# NixieBoard.net
KiCad netlist of a schematic drawn in EAGLE
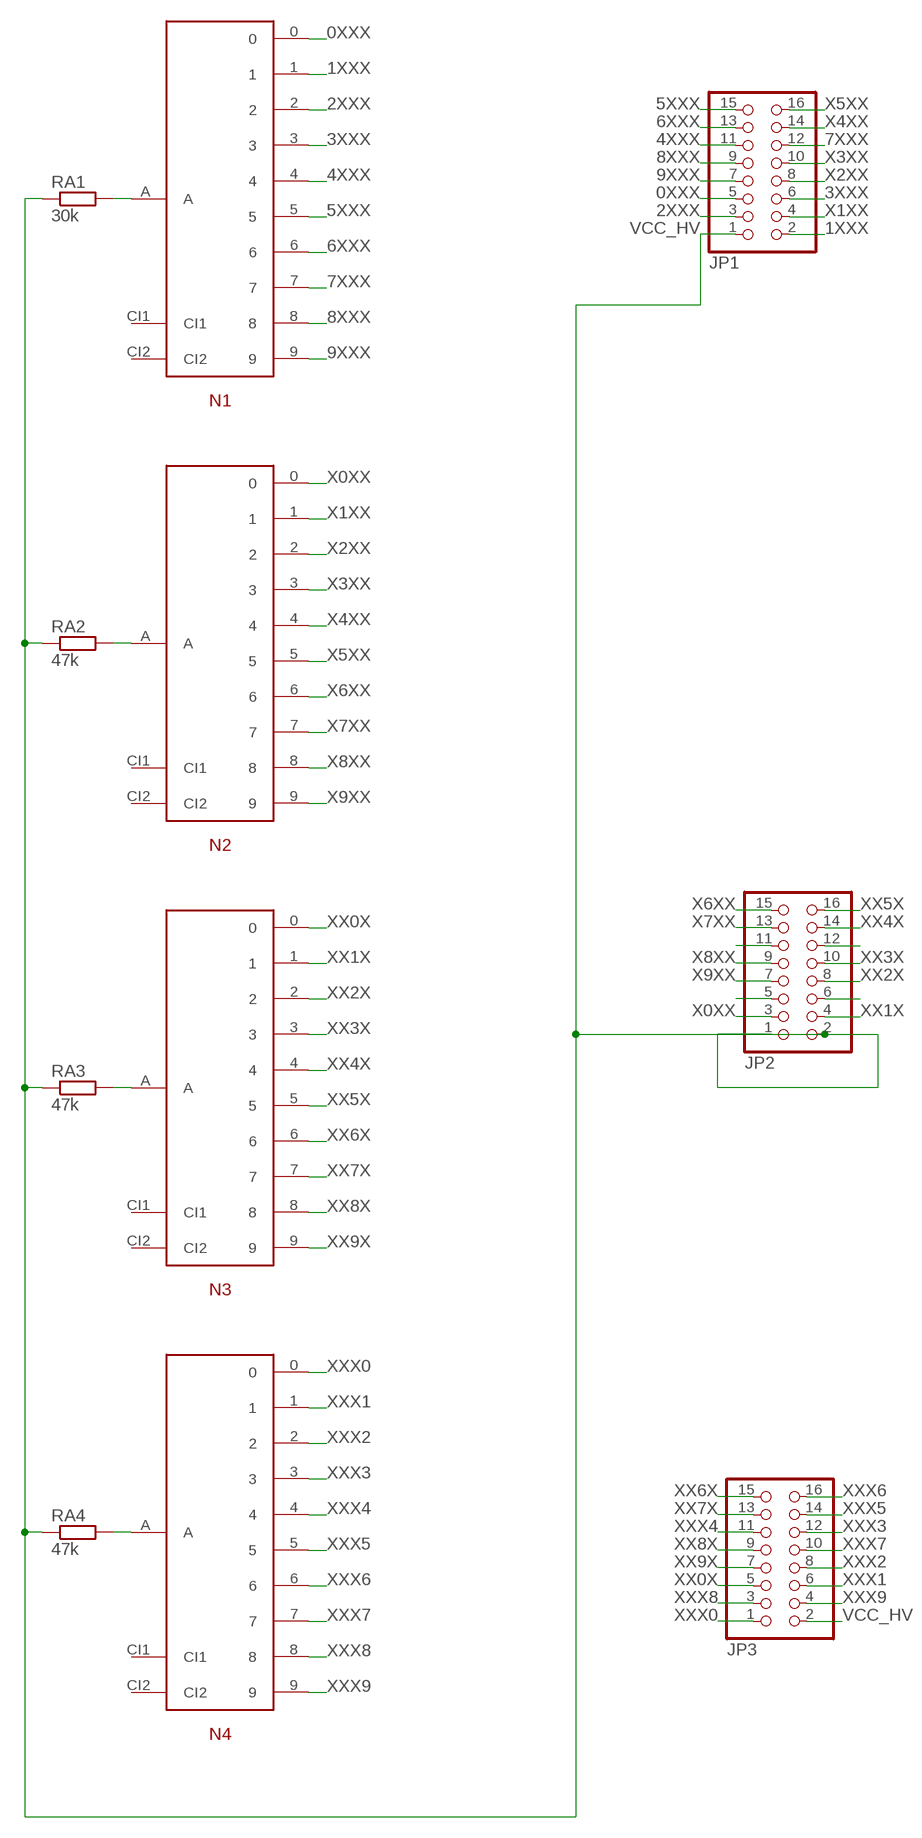
[diagram p0: schematic, sheet 1]

(export (version "E")
  (design (tool "Eeschema 10.0.6"))
  (components
    (comp (ref "JP1")
      (value "PINHD-2X8")
      (footprint "eagle-import:2X08")
      (libsource (lib "eagle-import") (part "PINHD-2X8"))
    )
    (comp (ref "JP2")
      (value "PINHD-2X8")
      (footprint "eagle-import:2X08")
      (libsource (lib "eagle-import") (part "PINHD-2X8"))
    )
    (comp (ref "JP3")
      (value "PINHD-2X8")
      (footprint "eagle-import:2X08")
      (libsource (lib "eagle-import") (part "PINHD-2X8"))
    )
    (comp (ref "N1")
      (value "F9057TUBE")
      (footprint "eagle-import:F9057PIN")
      (libsource (lib "eagle-import") (part "F9057TUBE"))
    )
    (comp (ref "N2")
      (value "F9057TUBE")
      (footprint "eagle-import:F9057PIN")
      (libsource (lib "eagle-import") (part "F9057TUBE"))
    )
    (comp (ref "N3")
      (value "F9057TUBE")
      (footprint "eagle-import:F9057PIN")
      (libsource (lib "eagle-import") (part "F9057TUBE"))
    )
    (comp (ref "N4")
      (value "F9057TUBE")
      (footprint "eagle-import:F9057PIN")
      (libsource (lib "eagle-import") (part "F9057TUBE"))
    )
    (comp (ref "RA1")
      (value "30k")
      (footprint "eagle-import:R2010")
      (libsource (lib "eagle-import") (part "R-EU_R2010"))
    )
    (comp (ref "RA2")
      (value "47k")
      (footprint "eagle-import:R2010")
      (libsource (lib "eagle-import") (part "R-EU_R2010"))
    )
    (comp (ref "RA3")
      (value "47k")
      (footprint "eagle-import:R2010")
      (libsource (lib "eagle-import") (part "R-EU_R2010"))
    )
    (comp (ref "RA4")
      (value "47k")
      (footprint "eagle-import:R2010")
      (libsource (lib "eagle-import") (part "R-EU_R2010"))
    )
  )
  (nets
    (net (code "1") (name "/0XXX") (class "Default")
      (node (ref "JP1") (pin "5") (pinfunction "5_5") (pintype "passive"))
      (node (ref "N1") (pin "0") (pinfunction "0_0") (pintype "bidirectional"))
    )
    (net (code "2") (name "/1XXX") (class "Default")
      (node (ref "JP1") (pin "2") (pinfunction "2_2") (pintype "passive"))
      (node (ref "N1") (pin "1") (pinfunction "1_1") (pintype "bidirectional"))
    )
    (net (code "3") (name "/2XXX") (class "Default")
      (node (ref "JP1") (pin "3") (pinfunction "3_3") (pintype "passive"))
      (node (ref "N1") (pin "2") (pinfunction "2_2") (pintype "bidirectional"))
    )
    (net (code "4") (name "/3XXX") (class "Default")
      (node (ref "JP1") (pin "6") (pinfunction "6_6") (pintype "passive"))
      (node (ref "N1") (pin "3") (pinfunction "3_3") (pintype "bidirectional"))
    )
    (net (code "5") (name "/4XXX") (class "Default")
      (node (ref "JP1") (pin "11") (pinfunction "11_11") (pintype "passive"))
      (node (ref "N1") (pin "4") (pinfunction "4_4") (pintype "bidirectional"))
    )
    (net (code "6") (name "/5XXX") (class "Default")
      (node (ref "JP1") (pin "15") (pinfunction "15_15") (pintype "passive"))
      (node (ref "N1") (pin "5") (pinfunction "5_5") (pintype "bidirectional"))
    )
    (net (code "7") (name "/6XXX") (class "Default")
      (node (ref "JP1") (pin "13") (pinfunction "13_13") (pintype "passive"))
      (node (ref "N1") (pin "6") (pinfunction "6_6") (pintype "bidirectional"))
    )
    (net (code "8") (name "/7XXX") (class "Default")
      (node (ref "JP1") (pin "12") (pinfunction "12_12") (pintype "passive"))
      (node (ref "N1") (pin "7") (pinfunction "7_7") (pintype "bidirectional"))
    )
    (net (code "9") (name "/8XXX") (class "Default")
      (node (ref "JP1") (pin "9") (pinfunction "9_9") (pintype "passive"))
      (node (ref "N1") (pin "8") (pinfunction "8_8") (pintype "bidirectional"))
    )
    (net (code "10") (name "/9XXX") (class "Default")
      (node (ref "JP1") (pin "7") (pinfunction "7_7") (pintype "passive"))
      (node (ref "N1") (pin "9") (pinfunction "9_9") (pintype "bidirectional"))
    )
    (net (code "11") (name "/VCC_HV") (class "Default")
      (node (ref "JP1") (pin "1") (pinfunction "1_1") (pintype "passive"))
      (node (ref "JP2") (pin "1") (pinfunction "1_1") (pintype "passive"))
      (node (ref "JP2") (pin "2") (pinfunction "2_2") (pintype "passive"))
      (node (ref "JP3") (pin "2") (pinfunction "2_2") (pintype "passive"))
      (node (ref "RA1") (pin "1") (pinfunction "1_1") (pintype "passive"))
      (node (ref "RA2") (pin "1") (pinfunction "1_1") (pintype "passive"))
      (node (ref "RA3") (pin "1") (pinfunction "1_1") (pintype "passive"))
      (node (ref "RA4") (pin "1") (pinfunction "1_1") (pintype "passive"))
    )
    (net (code "12") (name "/X0XX") (class "Default")
      (node (ref "JP2") (pin "3") (pinfunction "3_3") (pintype "passive"))
      (node (ref "N2") (pin "0") (pinfunction "0_0") (pintype "bidirectional"))
    )
    (net (code "13") (name "/X1XX") (class "Default")
      (node (ref "JP1") (pin "4") (pinfunction "4_4") (pintype "passive"))
      (node (ref "N2") (pin "1") (pinfunction "1_1") (pintype "bidirectional"))
    )
    (net (code "14") (name "/X2XX") (class "Default")
      (node (ref "JP1") (pin "8") (pinfunction "8_8") (pintype "passive"))
      (node (ref "N2") (pin "2") (pinfunction "2_2") (pintype "bidirectional"))
    )
    (net (code "15") (name "/X3XX") (class "Default")
      (node (ref "JP1") (pin "10") (pinfunction "10_10") (pintype "passive"))
      (node (ref "N2") (pin "3") (pinfunction "3_3") (pintype "bidirectional"))
    )
    (net (code "16") (name "/X4XX") (class "Default")
      (node (ref "JP1") (pin "14") (pinfunction "14_14") (pintype "passive"))
      (node (ref "N2") (pin "4") (pinfunction "4_4") (pintype "bidirectional"))
    )
    (net (code "17") (name "/X5XX") (class "Default")
      (node (ref "JP1") (pin "16") (pinfunction "16_16") (pintype "passive"))
      (node (ref "N2") (pin "5") (pinfunction "5_5") (pintype "bidirectional"))
    )
    (net (code "18") (name "/X6XX") (class "Default")
      (node (ref "JP2") (pin "15") (pinfunction "15_15") (pintype "passive"))
      (node (ref "N2") (pin "6") (pinfunction "6_6") (pintype "bidirectional"))
    )
    (net (code "19") (name "/X7XX") (class "Default")
      (node (ref "JP2") (pin "13") (pinfunction "13_13") (pintype "passive"))
      (node (ref "N2") (pin "7") (pinfunction "7_7") (pintype "bidirectional"))
    )
    (net (code "20") (name "/X8XX") (class "Default")
      (node (ref "JP2") (pin "9") (pinfunction "9_9") (pintype "passive"))
      (node (ref "N2") (pin "8") (pinfunction "8_8") (pintype "bidirectional"))
    )
    (net (code "21") (name "/X9XX") (class "Default")
      (node (ref "JP2") (pin "7") (pinfunction "7_7") (pintype "passive"))
      (node (ref "N2") (pin "9") (pinfunction "9_9") (pintype "bidirectional"))
    )
    (net (code "22") (name "/XX0X") (class "Default")
      (node (ref "JP3") (pin "5") (pinfunction "5_5") (pintype "passive"))
      (node (ref "N3") (pin "0") (pinfunction "0_0") (pintype "bidirectional"))
    )
    (net (code "23") (name "/XX1X") (class "Default")
      (node (ref "JP2") (pin "4") (pinfunction "4_4") (pintype "passive"))
      (node (ref "N3") (pin "1") (pinfunction "1_1") (pintype "bidirectional"))
    )
    (net (code "24") (name "/XX2X") (class "Default")
      (node (ref "JP2") (pin "8") (pinfunction "8_8") (pintype "passive"))
      (node (ref "N3") (pin "2") (pinfunction "2_2") (pintype "bidirectional"))
    )
    (net (code "25") (name "/XX3X") (class "Default")
      (node (ref "JP2") (pin "10") (pinfunction "10_10") (pintype "passive"))
      (node (ref "N3") (pin "3") (pinfunction "3_3") (pintype "bidirectional"))
    )
    (net (code "26") (name "/XX4X") (class "Default")
      (node (ref "JP2") (pin "14") (pinfunction "14_14") (pintype "passive"))
      (node (ref "N3") (pin "4") (pinfunction "4_4") (pintype "bidirectional"))
    )
    (net (code "27") (name "/XX5X") (class "Default")
      (node (ref "JP2") (pin "16") (pinfunction "16_16") (pintype "passive"))
      (node (ref "N3") (pin "5") (pinfunction "5_5") (pintype "bidirectional"))
    )
    (net (code "28") (name "/XX6X") (class "Default")
      (node (ref "JP3") (pin "15") (pinfunction "15_15") (pintype "passive"))
      (node (ref "N3") (pin "6") (pinfunction "6_6") (pintype "bidirectional"))
    )
    (net (code "29") (name "/XX7X") (class "Default")
      (node (ref "JP3") (pin "13") (pinfunction "13_13") (pintype "passive"))
      (node (ref "N3") (pin "7") (pinfunction "7_7") (pintype "bidirectional"))
    )
    (net (code "30") (name "/XX8X") (class "Default")
      (node (ref "JP3") (pin "9") (pinfunction "9_9") (pintype "passive"))
      (node (ref "N3") (pin "8") (pinfunction "8_8") (pintype "bidirectional"))
    )
    (net (code "31") (name "/XX9X") (class "Default")
      (node (ref "JP3") (pin "7") (pinfunction "7_7") (pintype "passive"))
      (node (ref "N3") (pin "9") (pinfunction "9_9") (pintype "bidirectional"))
    )
    (net (code "32") (name "/XXX0") (class "Default")
      (node (ref "JP3") (pin "1") (pinfunction "1_1") (pintype "passive"))
      (node (ref "N4") (pin "0") (pinfunction "0_0") (pintype "bidirectional"))
    )
    (net (code "33") (name "/XXX1") (class "Default")
      (node (ref "JP3") (pin "6") (pinfunction "6_6") (pintype "passive"))
      (node (ref "N4") (pin "1") (pinfunction "1_1") (pintype "bidirectional"))
    )
    (net (code "34") (name "/XXX2") (class "Default")
      (node (ref "JP3") (pin "8") (pinfunction "8_8") (pintype "passive"))
      (node (ref "N4") (pin "2") (pinfunction "2_2") (pintype "bidirectional"))
    )
    (net (code "35") (name "/XXX3") (class "Default")
      (node (ref "JP3") (pin "12") (pinfunction "12_12") (pintype "passive"))
      (node (ref "N4") (pin "3") (pinfunction "3_3") (pintype "bidirectional"))
    )
    (net (code "36") (name "/XXX4") (class "Default")
      (node (ref "JP3") (pin "11") (pinfunction "11_11") (pintype "passive"))
      (node (ref "N4") (pin "4") (pinfunction "4_4") (pintype "bidirectional"))
    )
    (net (code "37") (name "/XXX5") (class "Default")
      (node (ref "JP3") (pin "14") (pinfunction "14_14") (pintype "passive"))
      (node (ref "N4") (pin "5") (pinfunction "5_5") (pintype "bidirectional"))
    )
    (net (code "38") (name "/XXX6") (class "Default")
      (node (ref "JP3") (pin "16") (pinfunction "16_16") (pintype "passive"))
      (node (ref "N4") (pin "6") (pinfunction "6_6") (pintype "bidirectional"))
    )
    (net (code "39") (name "/XXX7") (class "Default")
      (node (ref "JP3") (pin "10") (pinfunction "10_10") (pintype "passive"))
      (node (ref "N4") (pin "7") (pinfunction "7_7") (pintype "bidirectional"))
    )
    (net (code "40") (name "/XXX8") (class "Default")
      (node (ref "JP3") (pin "3") (pinfunction "3_3") (pintype "passive"))
      (node (ref "N4") (pin "8") (pinfunction "8_8") (pintype "bidirectional"))
    )
    (net (code "41") (name "/XXX9") (class "Default")
      (node (ref "JP3") (pin "4") (pinfunction "4_4") (pintype "passive"))
      (node (ref "N4") (pin "9") (pinfunction "9_9") (pintype "bidirectional"))
    )
    (net (code "42") (name "Net-(N1-PadA)") (class "Default")
      (node (ref "N1") (pin "A") (pinfunction "A_A") (pintype "power_in"))
      (node (ref "RA1") (pin "2") (pinfunction "2_2") (pintype "passive"))
    )
    (net (code "43") (name "Net-(N2-PadA)") (class "Default")
      (node (ref "N2") (pin "A") (pinfunction "A_A") (pintype "power_in"))
      (node (ref "RA2") (pin "2") (pinfunction "2_2") (pintype "passive"))
    )
    (net (code "44") (name "Net-(N3-PadA)") (class "Default")
      (node (ref "N3") (pin "A") (pinfunction "A_A") (pintype "power_in"))
      (node (ref "RA3") (pin "2") (pinfunction "2_2") (pintype "passive"))
    )
    (net (code "45") (name "Net-(N4-PadA)") (class "Default")
      (node (ref "N4") (pin "A") (pinfunction "A_A") (pintype "power_in"))
      (node (ref "RA4") (pin "2") (pinfunction "2_2") (pintype "passive"))
    )
    (net (code "46") (name "unconnected-(JP2-Pad5)") (class "Default")
      (node (ref "JP2") (pin "5") (pinfunction "5_5") (pintype "passive"))
    )
    (net (code "47") (name "unconnected-(JP2-Pad6)") (class "Default")
      (node (ref "JP2") (pin "6") (pinfunction "6_6") (pintype "passive"))
    )
    (net (code "48") (name "unconnected-(JP2-Pad11)") (class "Default")
      (node (ref "JP2") (pin "11") (pinfunction "11_11") (pintype "passive"))
    )
    (net (code "49") (name "unconnected-(JP2-Pad12)") (class "Default")
      (node (ref "JP2") (pin "12") (pinfunction "12_12") (pintype "passive"))
    )
    (net (code "50") (name "unconnected-(N1-PadCI1)") (class "Default")
      (node (ref "N1") (pin "CI1") (pinfunction "CI1_CI1") (pintype "no_connect"))
    )
    (net (code "51") (name "unconnected-(N1-PadCI2)") (class "Default")
      (node (ref "N1") (pin "CI2") (pinfunction "CI2_CI2") (pintype "no_connect"))
    )
    (net (code "52") (name "unconnected-(N2-PadCI1)") (class "Default")
      (node (ref "N2") (pin "CI1") (pinfunction "CI1_CI1") (pintype "no_connect"))
    )
    (net (code "53") (name "unconnected-(N2-PadCI2)") (class "Default")
      (node (ref "N2") (pin "CI2") (pinfunction "CI2_CI2") (pintype "no_connect"))
    )
    (net (code "54") (name "unconnected-(N3-PadCI1)") (class "Default")
      (node (ref "N3") (pin "CI1") (pinfunction "CI1_CI1") (pintype "no_connect"))
    )
    (net (code "55") (name "unconnected-(N3-PadCI2)") (class "Default")
      (node (ref "N3") (pin "CI2") (pinfunction "CI2_CI2") (pintype "no_connect"))
    )
    (net (code "56") (name "unconnected-(N4-PadCI1)") (class "Default")
      (node (ref "N4") (pin "CI1") (pinfunction "CI1_CI1") (pintype "no_connect"))
    )
    (net (code "57") (name "unconnected-(N4-PadCI2)") (class "Default")
      (node (ref "N4") (pin "CI2") (pinfunction "CI2_CI2") (pintype "no_connect"))
    )
  )
)
